# main.net
KiCad netlist of a schematic drawn in Altium Designer
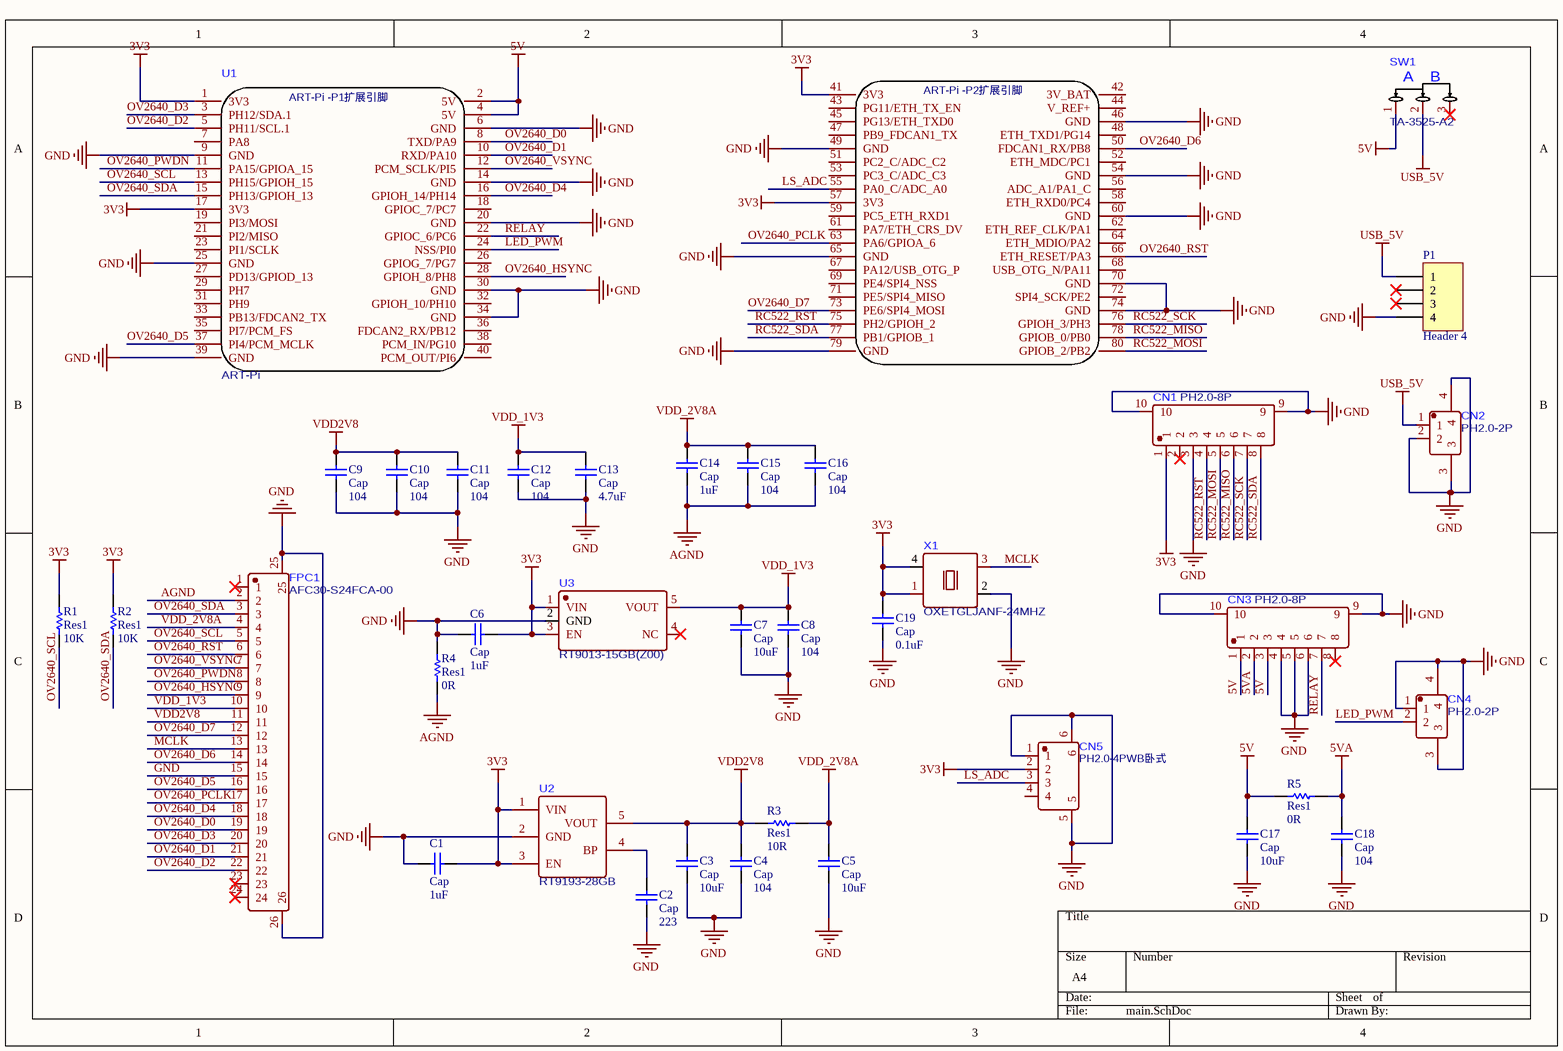
[diagram p0: main.SchDoc]

(export (version "E")
  (design (tool "Eeschema 10.0.6"))
  (components
    (comp (ref "C1")
      (value "Cap")
      (footprint "R0603")
      (description "Capacitor")
      (fields (field (name "ALTIUM_VALUE") "1uF") (field (name "PUBLISHER") "Altium Limited"))
      (libsource (lib "Miscellaneous Devices") (part "Cap"))
    )
    (comp (ref "C2")
      (value "Cap")
      (footprint "R0603")
      (description "Capacitor")
      (fields (field (name "ALTIUM_VALUE") "223") (field (name "PUBLISHER") "Altium Limited"))
      (libsource (lib "Miscellaneous Devices") (part "Cap"))
    )
    (comp (ref "C3")
      (value "Cap")
      (footprint "R0603")
      (description "Capacitor")
      (fields (field (name "ALTIUM_VALUE") "10uF") (field (name "PUBLISHER") "Altium Limited"))
      (libsource (lib "Miscellaneous Devices") (part "Cap"))
    )
    (comp (ref "C4")
      (value "Cap")
      (footprint "R0603")
      (description "Capacitor")
      (fields (field (name "ALTIUM_VALUE") "104") (field (name "PUBLISHER") "Altium Limited"))
      (libsource (lib "Miscellaneous Devices") (part "Cap"))
    )
    (comp (ref "C5")
      (value "Cap")
      (footprint "R0603")
      (description "Capacitor")
      (fields (field (name "ALTIUM_VALUE") "10uF") (field (name "PUBLISHER") "Altium Limited"))
      (libsource (lib "Miscellaneous Devices") (part "Cap"))
    )
    (comp (ref "C6")
      (value "Cap")
      (footprint "R0603")
      (description "Capacitor")
      (fields (field (name "ALTIUM_VALUE") "1uF") (field (name "PUBLISHER") "Altium Limited"))
      (libsource (lib "Miscellaneous Devices") (part "Cap"))
    )
    (comp (ref "C7")
      (value "Cap")
      (footprint "R0603")
      (description "Capacitor")
      (fields (field (name "ALTIUM_VALUE") "10uF") (field (name "PUBLISHER") "Altium Limited"))
      (libsource (lib "Miscellaneous Devices") (part "Cap"))
    )
    (comp (ref "C8")
      (value "Cap")
      (footprint "R0603")
      (description "Capacitor")
      (fields (field (name "ALTIUM_VALUE") "104") (field (name "PUBLISHER") "Altium Limited"))
      (libsource (lib "Miscellaneous Devices") (part "Cap"))
    )
    (comp (ref "C9")
      (value "Cap")
      (footprint "R0603")
      (description "Capacitor")
      (fields (field (name "ALTIUM_VALUE") "104") (field (name "PUBLISHER") "Altium Limited"))
      (libsource (lib "Miscellaneous Devices") (part "Cap"))
    )
    (comp (ref "C10")
      (value "Cap")
      (footprint "R0603")
      (description "Capacitor")
      (fields (field (name "ALTIUM_VALUE") "104") (field (name "PUBLISHER") "Altium Limited"))
      (libsource (lib "Miscellaneous Devices") (part "Cap"))
    )
    (comp (ref "C11")
      (value "Cap")
      (footprint "R0603")
      (description "Capacitor")
      (fields (field (name "ALTIUM_VALUE") "104") (field (name "PUBLISHER") "Altium Limited"))
      (libsource (lib "Miscellaneous Devices") (part "Cap"))
    )
    (comp (ref "C12")
      (value "Cap")
      (footprint "R0603")
      (description "Capacitor")
      (fields (field (name "ALTIUM_VALUE") "104") (field (name "PUBLISHER") "Altium Limited"))
      (libsource (lib "Miscellaneous Devices") (part "Cap"))
    )
    (comp (ref "C13")
      (value "Cap")
      (footprint "R0603")
      (description "Capacitor")
      (fields (field (name "ALTIUM_VALUE") "4.7uF") (field (name "PUBLISHER") "Altium Limited"))
      (libsource (lib "Miscellaneous Devices") (part "Cap"))
    )
    (comp (ref "C14")
      (value "Cap")
      (footprint "R0603")
      (description "Capacitor")
      (fields (field (name "ALTIUM_VALUE") "1uF") (field (name "PUBLISHER") "Altium Limited"))
      (libsource (lib "Miscellaneous Devices") (part "Cap"))
    )
    (comp (ref "C15")
      (value "Cap")
      (footprint "R0603")
      (description "Capacitor")
      (fields (field (name "ALTIUM_VALUE") "104") (field (name "PUBLISHER") "Altium Limited"))
      (libsource (lib "Miscellaneous Devices") (part "Cap"))
    )
    (comp (ref "C16")
      (value "Cap")
      (footprint "R0603")
      (description "Capacitor")
      (fields (field (name "ALTIUM_VALUE") "104") (field (name "PUBLISHER") "Altium Limited"))
      (libsource (lib "Miscellaneous Devices") (part "Cap"))
    )
    (comp (ref "C17")
      (value "Cap")
      (footprint "R0603")
      (description "Capacitor")
      (fields (field (name "ALTIUM_VALUE") "10uF") (field (name "PUBLISHER") "Altium Limited"))
      (libsource (lib "Miscellaneous Devices") (part "Cap"))
    )
    (comp (ref "C18")
      (value "Cap")
      (footprint "R0603")
      (description "Capacitor")
      (fields (field (name "ALTIUM_VALUE") "104") (field (name "PUBLISHER") "Altium Limited"))
      (libsource (lib "Miscellaneous Devices") (part "Cap"))
    )
    (comp (ref "C19")
      (value "Cap")
      (footprint "R0603")
      (description "Capacitor")
      (fields (field (name "ALTIUM_VALUE") "0.1uF") (field (name "PUBLISHER") "Altium Limited"))
      (libsource (lib "Miscellaneous Devices") (part "Cap"))
    )
    (comp (ref "CN1")
      (value "PH2.0-8P")
      (footprint "CONN-SMD_X2016WRS-08-9TSW")
      (libsource (lib "PH2.0-8P_2021-08-20") (part "PH2.0-8P"))
    )
    (comp (ref "CN2")
      (value "PH2.0-2P")
      (footprint "CONN-SMD_PH2.0-1X2PW")
      (libsource (lib "PH2.0-2P_2021-08-20") (part "PH2.0-2P"))
    )
    (comp (ref "CN3")
      (value "PH2.0-8P")
      (footprint "CONN-SMD_X2016WRS-08-9TSW")
      (libsource (lib "PH2.0-8P_2021-08-20") (part "PH2.0-8P"))
    )
    (comp (ref "CN4")
      (value "PH2.0-2P")
      (footprint "CONN-SMD_PH2.0-1X2PW")
      (libsource (lib "PH2.0-2P_2021-08-20") (part "PH2.0-2P"))
    )
    (comp (ref "CN5")
      (value "PH2.0-4PWB卧式")
      (footprint "CONN-SMD_PH2.0-4PWB")
      (libsource (lib "PH2.0-4PWB卧式_2021-08-21") (part "PH2.0-4PWB卧式"))
    )
    (comp (ref "FPC1")
      (value "AFC30-S24FCA-00")
      (footprint "FPC-SMD_AFC30-S24FCA-00")
      (libsource (lib "AFC30-S24FCA-00_2021-08-20") (part "AFC30-S24FCA-00"))
    )
    (comp (ref "P1")
      (value "Header 4")
      (footprint "HDR1X4")
      (description "Header, 4-Pin")
      (fields (field (name "PUBLISHER") "Altium Limited"))
      (libsource (lib "Miscellaneous Connectors") (part "Header 4"))
    )
    (comp (ref "R1")
      (value "Res1")
      (footprint "R0603")
      (description "Resistor")
      (fields (field (name "ALTIUM_VALUE") "10K") (field (name "PUBLISHER") "Altium Limited"))
      (libsource (lib "Miscellaneous Devices") (part "Res1"))
    )
    (comp (ref "R2")
      (value "Res1")
      (footprint "R0603")
      (description "Resistor")
      (fields (field (name "ALTIUM_VALUE") "10K") (field (name "PUBLISHER") "Altium Limited"))
      (libsource (lib "Miscellaneous Devices") (part "Res1"))
    )
    (comp (ref "R3")
      (value "Res1")
      (footprint "R0603")
      (description "Resistor")
      (fields (field (name "ALTIUM_VALUE") "10R") (field (name "PUBLISHER") "Altium Limited"))
      (libsource (lib "Miscellaneous Devices") (part "Res1"))
    )
    (comp (ref "R4")
      (value "Res1")
      (footprint "R0603")
      (description "Resistor")
      (fields (field (name "ALTIUM_VALUE") "0R") (field (name "PUBLISHER") "Altium Limited"))
      (libsource (lib "Miscellaneous Devices") (part "Res1"))
    )
    (comp (ref "R5")
      (value "Res1")
      (footprint "R0603")
      (description "Resistor")
      (fields (field (name "ALTIUM_VALUE") "0R") (field (name "PUBLISHER") "Altium Limited"))
      (libsource (lib "Miscellaneous Devices") (part "Res1"))
    )
    (comp (ref "SW1")
      (value "TA-3525-A2")
      (footprint "SW-SMD_3P-L9.1-W3.5-P2.50-EH6.8")
      (libsource (lib "TA-3525-A2_2021-08-20") (part "TA-3525-A2"))
    )
    (comp (ref "U1")
      (value "ART-Pi")
      (footprint "PCBComponent_1 - duplicate")
      (libsource (lib "ART-Pi") (part "ART-Pi"))
    )
    (comp (ref "U2")
      (value "RT9193-28GB")
      (footprint "SOT-23-5_L3.0-W1.7-P0.95-LS2.8-BR")
      (libsource (lib "RT9193-28GB_2021-08-20") (part "RT9193-28GB"))
    )
    (comp (ref "U3")
      (value "RT9013-15GB(Z00)")
      (footprint "SOT-23-5_L3.0-W1.7-P0.95-LS2.8-BR")
      (libsource (lib "RT9013-15GB(Z00)_2021-08-20") (part "RT9013-15GB(Z00)"))
    )
    (comp (ref "X1")
      (value "OXETGLJANF-24MHZ")
      (footprint "OSC-SMD_4P-L3.2-W2.5-BL")
      (libsource (lib "OXETGLJANF-24MHZ_2021-08-21") (part "OXETGLJANF-24MHZ"))
    )
  )
  (nets
    (net (code "1") (name "/LED_PWM") (class "Default")
      (node (ref "CN4") (pin "2") (pinfunction "2_2") (pintype "passive"))
      (node (ref "U1") (pin "24") (pinfunction "NSS/PI0_24") (pintype "passive"))
    )
    (net (code "2") (name "/LS_ADC") (class "Default")
      (node (ref "CN5") (pin "3") (pinfunction "3_3") (pintype "passive"))
      (node (ref "U1") (pin "55") (pinfunction "PA0_C/ADC_A0_55") (pintype "passive"))
    )
    (net (code "3") (name "/MCLK") (class "Default")
      (node (ref "FPC1") (pin "13") (pinfunction "13_13") (pintype "passive"))
      (node (ref "X1") (pin "3") (pinfunction "OUT_3") (pintype "passive"))
    )
    (net (code "4") (name "/OV2640_D0") (class "Default")
      (node (ref "FPC1") (pin "19") (pinfunction "19_19") (pintype "passive"))
      (node (ref "U1") (pin "8") (pinfunction "TXD/PA9_8") (pintype "passive"))
    )
    (net (code "5") (name "/OV2640_D1") (class "Default")
      (node (ref "FPC1") (pin "21") (pinfunction "21_21") (pintype "passive"))
      (node (ref "U1") (pin "10") (pinfunction "RXD/PA10_10") (pintype "passive"))
    )
    (net (code "6") (name "/OV2640_D2") (class "Default")
      (node (ref "FPC1") (pin "22") (pinfunction "22_22") (pintype "passive"))
      (node (ref "U1") (pin "5") (pinfunction "PH11/SCL.1_5") (pintype "passive"))
    )
    (net (code "7") (name "/OV2640_D3") (class "Default")
      (node (ref "FPC1") (pin "20") (pinfunction "20_20") (pintype "passive"))
      (node (ref "U1") (pin "3") (pinfunction "PH12/SDA.1_3") (pintype "passive"))
    )
    (net (code "8") (name "/OV2640_D4") (class "Default")
      (node (ref "FPC1") (pin "18") (pinfunction "18_18") (pintype "passive"))
      (node (ref "U1") (pin "16") (pinfunction "GPIOH_14/PH14_16") (pintype "passive"))
    )
    (net (code "9") (name "/OV2640_D5") (class "Default")
      (node (ref "FPC1") (pin "16") (pinfunction "16_16") (pintype "passive"))
      (node (ref "U1") (pin "37") (pinfunction "PI4/PCM_MCLK_37") (pintype "passive"))
    )
    (net (code "10") (name "/OV2640_D6") (class "Default")
      (node (ref "FPC1") (pin "14") (pinfunction "14_14") (pintype "passive"))
      (node (ref "U1") (pin "50") (pinfunction "FDCAN1_RX/PB8_50") (pintype "passive"))
    )
    (net (code "11") (name "/OV2640_D7") (class "Default")
      (node (ref "FPC1") (pin "12") (pinfunction "12_12") (pintype "passive"))
      (node (ref "U1") (pin "73") (pinfunction "PE6/SPI4_MOSI_73") (pintype "passive"))
    )
    (net (code "12") (name "/OV2640_HSYNC") (class "Default")
      (node (ref "FPC1") (pin "9") (pinfunction "9_9") (pintype "passive"))
      (node (ref "U1") (pin "28") (pinfunction "GPIOH_8/PH8_28") (pintype "passive"))
    )
    (net (code "13") (name "/OV2640_PCLK") (class "Default")
      (node (ref "FPC1") (pin "17") (pinfunction "17_17") (pintype "passive"))
      (node (ref "U1") (pin "63") (pinfunction "PA6/GPIOA_6_63") (pintype "passive"))
    )
    (net (code "14") (name "/OV2640_PWDN") (class "Default")
      (node (ref "FPC1") (pin "8") (pinfunction "8_8") (pintype "passive"))
      (node (ref "U1") (pin "11") (pinfunction "PA15/GPIOA_15_11") (pintype "passive"))
    )
    (net (code "15") (name "/OV2640_RST") (class "Default")
      (node (ref "FPC1") (pin "6") (pinfunction "6_6") (pintype "passive"))
      (node (ref "U1") (pin "66") (pinfunction "ETH_RESET/PA3_66") (pintype "passive"))
    )
    (net (code "16") (name "/OV2640_SCL") (class "Default")
      (node (ref "FPC1") (pin "5") (pinfunction "5_5") (pintype "passive"))
      (node (ref "R1") (pin "1") (pinfunction "1_1") (pintype "passive"))
      (node (ref "U1") (pin "13") (pinfunction "PH15/GPIOH_15_13") (pintype "passive"))
    )
    (net (code "17") (name "/OV2640_SDA") (class "Default")
      (node (ref "FPC1") (pin "3") (pinfunction "3_3") (pintype "passive"))
      (node (ref "R2") (pin "1") (pinfunction "1_1") (pintype "passive"))
      (node (ref "U1") (pin "15") (pinfunction "PH13/GPIOH_13_15") (pintype "passive"))
    )
    (net (code "18") (name "/OV2640_VSYNC") (class "Default")
      (node (ref "FPC1") (pin "7") (pinfunction "7_7") (pintype "passive"))
      (node (ref "U1") (pin "12") (pinfunction "PCM_SCLK/PI5_12") (pintype "passive"))
    )
    (net (code "19") (name "/RC522_MISO") (class "Default")
      (node (ref "CN1") (pin "6") (pinfunction "6_6") (pintype "passive"))
      (node (ref "U1") (pin "78") (pinfunction "GPIOB_0/PB0_78") (pintype "passive"))
    )
    (net (code "20") (name "/RC522_MOSI") (class "Default")
      (node (ref "CN1") (pin "5") (pinfunction "5_5") (pintype "passive"))
      (node (ref "U1") (pin "80") (pinfunction "GPIOB_2/PB2_80") (pintype "passive"))
    )
    (net (code "21") (name "/RC522_RST") (class "Default")
      (node (ref "CN1") (pin "4") (pinfunction "4_4") (pintype "passive"))
      (node (ref "U1") (pin "75") (pinfunction "PH2/GPIOH_2_75") (pintype "passive"))
    )
    (net (code "22") (name "/RC522_SCK") (class "Default")
      (node (ref "CN1") (pin "7") (pinfunction "7_7") (pintype "passive"))
      (node (ref "U1") (pin "76") (pinfunction "GPIOH_3/PH3_76") (pintype "passive"))
    )
    (net (code "23") (name "/RC522_SDA") (class "Default")
      (node (ref "CN1") (pin "8") (pinfunction "8_8") (pintype "passive"))
      (node (ref "U1") (pin "77") (pinfunction "PB1/GPIOB_1_77") (pintype "passive"))
    )
    (net (code "24") (name "/RELAY") (class "Default")
      (node (ref "CN3") (pin "7") (pinfunction "7_7") (pintype "passive"))
      (node (ref "U1") (pin "22") (pinfunction "GPIOC_6/PC6_22") (pintype "passive"))
    )
    (net (code "25") (name "3V3") (class "Default")
      (node (ref "C1") (pin "1") (pinfunction "1_1") (pintype "passive"))
      (node (ref "C19") (pin "2") (pinfunction "2_2") (pintype "passive"))
      (node (ref "C6") (pin "1") (pinfunction "1_1") (pintype "passive"))
      (node (ref "CN1") (pin "1") (pinfunction "1_1") (pintype "passive"))
      (node (ref "CN5") (pin "2") (pinfunction "2_2") (pintype "passive"))
      (node (ref "R1") (pin "2") (pinfunction "2_2") (pintype "passive"))
      (node (ref "R2") (pin "2") (pinfunction "2_2") (pintype "passive"))
      (node (ref "U1") (pin "1") (pinfunction "3V3_1") (pintype "passive"))
      (node (ref "U1") (pin "17") (pinfunction "3V3_17") (pintype "passive"))
      (node (ref "U1") (pin "41") (pinfunction "3V3_41") (pintype "passive"))
      (node (ref "U1") (pin "57") (pinfunction "3V3_57") (pintype "passive"))
      (node (ref "U2") (pin "1") (pinfunction "VIN_1") (pintype "passive"))
      (node (ref "U2") (pin "3") (pinfunction "EN_3") (pintype "passive"))
      (node (ref "U3") (pin "1") (pinfunction "VIN_1") (pintype "passive"))
      (node (ref "U3") (pin "3") (pinfunction "EN_3") (pintype "passive"))
      (node (ref "X1") (pin "1") (pinfunction "tri_1") (pintype "passive"))
      (node (ref "X1") (pin "4") (pinfunction "VCC_4") (pintype "passive"))
    )
    (net (code "26") (name "5V") (class "Default")
      (node (ref "C17") (pin "2") (pinfunction "2_2") (pintype "passive"))
      (node (ref "CN3") (pin "1") (pinfunction "1_1") (pintype "passive"))
      (node (ref "CN3") (pin "3") (pinfunction "3_3") (pintype "passive"))
      (node (ref "R5") (pin "1") (pinfunction "1_1") (pintype "passive"))
      (node (ref "SW1") (pin "1") (pinfunction "1_1") (pintype "passive"))
      (node (ref "U1") (pin "2") (pinfunction "5V_2") (pintype "passive"))
      (node (ref "U1") (pin "4") (pinfunction "5V_4") (pintype "passive"))
    )
    (net (code "27") (name "5VA") (class "Default")
      (node (ref "C18") (pin "2") (pinfunction "2_2") (pintype "passive"))
      (node (ref "CN3") (pin "2") (pinfunction "2_2") (pintype "passive"))
      (node (ref "R5") (pin "2") (pinfunction "2_2") (pintype "passive"))
    )
    (net (code "28") (name "AGND") (class "Default")
      (node (ref "C14") (pin "1") (pinfunction "1_1") (pintype "passive"))
      (node (ref "C15") (pin "1") (pinfunction "1_1") (pintype "passive"))
      (node (ref "C16") (pin "1") (pinfunction "1_1") (pintype "passive"))
      (node (ref "FPC1") (pin "2") (pinfunction "2_2") (pintype "passive"))
      (node (ref "R4") (pin "1") (pinfunction "1_1") (pintype "passive"))
    )
    (net (code "29") (name "GND") (class "Default")
      (node (ref "C1") (pin "2") (pinfunction "2_2") (pintype "passive"))
      (node (ref "C10") (pin "1") (pinfunction "1_1") (pintype "passive"))
      (node (ref "C11") (pin "1") (pinfunction "1_1") (pintype "passive"))
      (node (ref "C12") (pin "1") (pinfunction "1_1") (pintype "passive"))
      (node (ref "C13") (pin "1") (pinfunction "1_1") (pintype "passive"))
      (node (ref "C17") (pin "1") (pinfunction "1_1") (pintype "passive"))
      (node (ref "C18") (pin "1") (pinfunction "1_1") (pintype "passive"))
      (node (ref "C19") (pin "1") (pinfunction "1_1") (pintype "passive"))
      (node (ref "C2") (pin "1") (pinfunction "1_1") (pintype "passive"))
      (node (ref "C3") (pin "1") (pinfunction "1_1") (pintype "passive"))
      (node (ref "C4") (pin "1") (pinfunction "1_1") (pintype "passive"))
      (node (ref "C5") (pin "1") (pinfunction "1_1") (pintype "passive"))
      (node (ref "C6") (pin "2") (pinfunction "2_2") (pintype "passive"))
      (node (ref "C7") (pin "1") (pinfunction "1_1") (pintype "passive"))
      (node (ref "C8") (pin "1") (pinfunction "1_1") (pintype "passive"))
      (node (ref "C9") (pin "1") (pinfunction "1_1") (pintype "passive"))
      (node (ref "CN1") (pin "10") (pinfunction "10_10") (pintype "passive"))
      (node (ref "CN1") (pin "3") (pinfunction "3_3") (pintype "passive"))
      (node (ref "CN1") (pin "9") (pinfunction "9_9") (pintype "passive"))
      (node (ref "CN2") (pin "2") (pinfunction "2_2") (pintype "passive"))
      (node (ref "CN2") (pin "3") (pinfunction "3_3") (pintype "passive"))
      (node (ref "CN2") (pin "4") (pinfunction "4_4") (pintype "passive"))
      (node (ref "CN3") (pin "10") (pinfunction "10_10") (pintype "passive"))
      (node (ref "CN3") (pin "4") (pinfunction "4_4") (pintype "passive"))
      (node (ref "CN3") (pin "5") (pinfunction "5_5") (pintype "passive"))
      (node (ref "CN3") (pin "6") (pinfunction "6_6") (pintype "passive"))
      (node (ref "CN3") (pin "9") (pinfunction "9_9") (pintype "passive"))
      (node (ref "CN4") (pin "1") (pinfunction "1_1") (pintype "passive"))
      (node (ref "CN4") (pin "3") (pinfunction "3_3") (pintype "passive"))
      (node (ref "CN4") (pin "4") (pinfunction "4_4") (pintype "passive"))
      (node (ref "CN5") (pin "1") (pinfunction "1_1") (pintype "passive"))
      (node (ref "CN5") (pin "5") (pinfunction "5_5") (pintype "passive"))
      (node (ref "CN5") (pin "6") (pinfunction "6_6") (pintype "passive"))
      (node (ref "FPC1") (pin "15") (pinfunction "15_15") (pintype "passive"))
      (node (ref "FPC1") (pin "25") (pinfunction "25_25") (pintype "passive"))
      (node (ref "FPC1") (pin "26") (pinfunction "26_26") (pintype "passive"))
      (node (ref "P1") (pin "4") (pinfunction "4_4") (pintype "passive"))
      (node (ref "R4") (pin "2") (pinfunction "2_2") (pintype "passive"))
      (node (ref "U1") (pin "14") (pinfunction "GND_14") (pintype "passive"))
      (node (ref "U1") (pin "20") (pinfunction "GND_20") (pintype "passive"))
      (node (ref "U1") (pin "25") (pinfunction "GND_25") (pintype "passive"))
      (node (ref "U1") (pin "30") (pinfunction "GND_30") (pintype "passive"))
      (node (ref "U1") (pin "34") (pinfunction "GND_34") (pintype "passive"))
      (node (ref "U1") (pin "39") (pinfunction "GND_39") (pintype "passive"))
      (node (ref "U1") (pin "46") (pinfunction "GND_46") (pintype "passive"))
      (node (ref "U1") (pin "49") (pinfunction "GND_49") (pintype "passive"))
      (node (ref "U1") (pin "54") (pinfunction "GND_54") (pintype "passive"))
      (node (ref "U1") (pin "6") (pinfunction "GND_6") (pintype "passive"))
      (node (ref "U1") (pin "60") (pinfunction "GND_60") (pintype "passive"))
      (node (ref "U1") (pin "65") (pinfunction "GND_65") (pintype "passive"))
      (node (ref "U1") (pin "70") (pinfunction "GND_70") (pintype "passive"))
      (node (ref "U1") (pin "74") (pinfunction "GND_74") (pintype "passive"))
      (node (ref "U1") (pin "79") (pinfunction "GND_79") (pintype "passive"))
      (node (ref "U1") (pin "9") (pinfunction "GND_9") (pintype "passive"))
      (node (ref "U2") (pin "2") (pinfunction "GND_2") (pintype "passive"))
      (node (ref "U3") (pin "2") (pinfunction "GND_2") (pintype "passive"))
      (node (ref "X1") (pin "2") (pinfunction "GND_2") (pintype "passive"))
    )
    (net (code "30") (name "Net-(U2-BP)") (class "Default")
      (node (ref "C2") (pin "2") (pinfunction "2_2") (pintype "passive"))
      (node (ref "U2") (pin "4") (pinfunction "BP_4") (pintype "passive"))
    )
    (net (code "31") (name "USB_5V") (class "Default")
      (node (ref "CN2") (pin "1") (pinfunction "1_1") (pintype "passive"))
      (node (ref "P1") (pin "1") (pinfunction "1_1") (pintype "passive"))
      (node (ref "SW1") (pin "2") (pinfunction "2_2") (pintype "passive"))
    )
    (net (code "32") (name "VDD2V8") (class "Default")
      (node (ref "C10") (pin "2") (pinfunction "2_2") (pintype "passive"))
      (node (ref "C11") (pin "2") (pinfunction "2_2") (pintype "passive"))
      (node (ref "C3") (pin "2") (pinfunction "2_2") (pintype "passive"))
      (node (ref "C4") (pin "2") (pinfunction "2_2") (pintype "passive"))
      (node (ref "C9") (pin "2") (pinfunction "2_2") (pintype "passive"))
      (node (ref "FPC1") (pin "11") (pinfunction "11_11") (pintype "passive"))
      (node (ref "R3") (pin "1") (pinfunction "1_1") (pintype "passive"))
      (node (ref "U2") (pin "5") (pinfunction "VOUT_5") (pintype "passive"))
    )
    (net (code "33") (name "VDD_1V3") (class "Default")
      (node (ref "C12") (pin "2") (pinfunction "2_2") (pintype "passive"))
      (node (ref "C13") (pin "2") (pinfunction "2_2") (pintype "passive"))
      (node (ref "C7") (pin "2") (pinfunction "2_2") (pintype "passive"))
      (node (ref "C8") (pin "2") (pinfunction "2_2") (pintype "passive"))
      (node (ref "FPC1") (pin "10") (pinfunction "10_10") (pintype "passive"))
      (node (ref "U3") (pin "5") (pinfunction "VOUT_5") (pintype "passive"))
    )
    (net (code "34") (name "VDD_2V8A") (class "Default")
      (node (ref "C14") (pin "2") (pinfunction "2_2") (pintype "passive"))
      (node (ref "C15") (pin "2") (pinfunction "2_2") (pintype "passive"))
      (node (ref "C16") (pin "2") (pinfunction "2_2") (pintype "passive"))
      (node (ref "C5") (pin "2") (pinfunction "2_2") (pintype "passive"))
      (node (ref "FPC1") (pin "4") (pinfunction "4_4") (pintype "passive"))
      (node (ref "R3") (pin "2") (pinfunction "2_2") (pintype "passive"))
    )
    (net (code "35") (name "unconnected-(CN1-Pad2)") (class "Default")
      (node (ref "CN1") (pin "2") (pinfunction "2_2") (pintype "passive+no_connect"))
    )
    (net (code "36") (name "unconnected-(CN3-Pad8)") (class "Default")
      (node (ref "CN3") (pin "8") (pinfunction "8_8") (pintype "passive+no_connect"))
    )
    (net (code "37") (name "unconnected-(CN5-Pad4)") (class "Default")
      (node (ref "CN5") (pin "4") (pinfunction "4_4") (pintype "passive"))
    )
    (net (code "38") (name "unconnected-(FPC1-Pad1)") (class "Default")
      (node (ref "FPC1") (pin "1") (pinfunction "1_1") (pintype "passive+no_connect"))
    )
    (net (code "39") (name "unconnected-(FPC1-Pad23)") (class "Default")
      (node (ref "FPC1") (pin "23") (pinfunction "23_23") (pintype "passive+no_connect"))
    )
    (net (code "40") (name "unconnected-(FPC1-Pad24)") (class "Default")
      (node (ref "FPC1") (pin "24") (pinfunction "24_24") (pintype "passive+no_connect"))
    )
    (net (code "41") (name "unconnected-(P1-Pad2)") (class "Default")
      (node (ref "P1") (pin "2") (pinfunction "2_2") (pintype "passive+no_connect"))
    )
    (net (code "42") (name "unconnected-(P1-Pad3)") (class "Default")
      (node (ref "P1") (pin "3") (pinfunction "3_3") (pintype "passive+no_connect"))
    )
    (net (code "43") (name "unconnected-(SW1-Pad3)") (class "Default")
      (node (ref "SW1") (pin "3") (pinfunction "3_3") (pintype "passive+no_connect"))
    )
    (net (code "44") (name "unconnected-(U1-3V_BAT-Pad42)") (class "Default")
      (node (ref "U1") (pin "42") (pinfunction "3V_BAT_42") (pintype "passive"))
    )
    (net (code "45") (name "unconnected-(U1-ADC_A1{slash}PA1_C-Pad56)") (class "Default")
      (node (ref "U1") (pin "56") (pinfunction "ADC_A1/PA1_C_56") (pintype "passive"))
    )
    (net (code "46") (name "unconnected-(U1-ETH_MDC{slash}PC1-Pad52)") (class "Default")
      (node (ref "U1") (pin "52") (pinfunction "ETH_MDC/PC1_52") (pintype "passive"))
    )
    (net (code "47") (name "unconnected-(U1-ETH_MDIO{slash}PA2-Pad64)") (class "Default")
      (node (ref "U1") (pin "64") (pinfunction "ETH_MDIO/PA2_64") (pintype "passive"))
    )
    (net (code "48") (name "unconnected-(U1-ETH_REF_CLK{slash}PA1-Pad62)") (class "Default")
      (node (ref "U1") (pin "62") (pinfunction "ETH_REF_CLK/PA1_62") (pintype "passive"))
    )
    (net (code "49") (name "unconnected-(U1-ETH_RXD0{slash}PC4-Pad58)") (class "Default")
      (node (ref "U1") (pin "58") (pinfunction "ETH_RXD0/PC4_58") (pintype "passive"))
    )
    (net (code "50") (name "unconnected-(U1-ETH_TXD1{slash}PG14-Pad48)") (class "Default")
      (node (ref "U1") (pin "48") (pinfunction "ETH_TXD1/PG14_48") (pintype "passive"))
    )
    (net (code "51") (name "unconnected-(U1-FDCAN2_RX{slash}PB12-Pad36)") (class "Default")
      (node (ref "U1") (pin "36") (pinfunction "FDCAN2_RX/PB12_36") (pintype "passive"))
    )
    (net (code "52") (name "unconnected-(U1-GPIOC_7{slash}PC7-Pad18)") (class "Default")
      (node (ref "U1") (pin "18") (pinfunction "GPIOC_7/PC7_18") (pintype "passive"))
    )
    (net (code "53") (name "unconnected-(U1-GPIOG_7{slash}PG7-Pad26)") (class "Default")
      (node (ref "U1") (pin "26") (pinfunction "GPIOG_7/PG7_26") (pintype "passive"))
    )
    (net (code "54") (name "unconnected-(U1-GPIOH_10{slash}PH10-Pad32)") (class "Default")
      (node (ref "U1") (pin "32") (pinfunction "GPIOH_10/PH10_32") (pintype "passive"))
    )
    (net (code "55") (name "unconnected-(U1-PA7{slash}ETH_CRS_DV-Pad61)") (class "Default")
      (node (ref "U1") (pin "61") (pinfunction "PA7/ETH_CRS_DV_61") (pintype "passive"))
    )
    (net (code "56") (name "unconnected-(U1-PA8-Pad7)") (class "Default")
      (node (ref "U1") (pin "7") (pinfunction "PA8_7") (pintype "passive"))
    )
    (net (code "57") (name "unconnected-(U1-PA12{slash}USB_OTG_P-Pad67)") (class "Default")
      (node (ref "U1") (pin "67") (pinfunction "PA12/USB_OTG_P_67") (pintype "passive"))
    )
    (net (code "58") (name "unconnected-(U1-PB9_FDCAN1_TX-Pad47)") (class "Default")
      (node (ref "U1") (pin "47") (pinfunction "PB9_FDCAN1_TX_47") (pintype "passive"))
    )
    (net (code "59") (name "unconnected-(U1-PB13{slash}FDCAN2_TX-Pad33)") (class "Default")
      (node (ref "U1") (pin "33") (pinfunction "PB13/FDCAN2_TX_33") (pintype "passive"))
    )
    (net (code "60") (name "unconnected-(U1-PC2_C{slash}ADC_C2-Pad51)") (class "Default")
      (node (ref "U1") (pin "51") (pinfunction "PC2_C/ADC_C2_51") (pintype "passive"))
    )
    (net (code "61") (name "unconnected-(U1-PC3_C{slash}ADC_C3-Pad53)") (class "Default")
      (node (ref "U1") (pin "53") (pinfunction "PC3_C/ADC_C3_53") (pintype "passive"))
    )
    (net (code "62") (name "unconnected-(U1-PC5_ETH_RXD1-Pad59)") (class "Default")
      (node (ref "U1") (pin "59") (pinfunction "PC5_ETH_RXD1_59") (pintype "passive"))
    )
    (net (code "63") (name "unconnected-(U1-PCM_IN{slash}PG10-Pad38)") (class "Default")
      (node (ref "U1") (pin "38") (pinfunction "PCM_IN/PG10_38") (pintype "passive"))
    )
    (net (code "64") (name "unconnected-(U1-PCM_OUT{slash}PI6-Pad40)") (class "Default")
      (node (ref "U1") (pin "40") (pinfunction "PCM_OUT/PI6_40") (pintype "passive"))
    )
    (net (code "65") (name "unconnected-(U1-PD13{slash}GPIOD_13-Pad27)") (class "Default")
      (node (ref "U1") (pin "27") (pinfunction "PD13/GPIOD_13_27") (pintype "passive"))
    )
    (net (code "66") (name "unconnected-(U1-PE4{slash}SPI4_NSS-Pad69)") (class "Default")
      (node (ref "U1") (pin "69") (pinfunction "PE4/SPI4_NSS_69") (pintype "passive"))
    )
    (net (code "67") (name "unconnected-(U1-PE5{slash}SPI4_MISO-Pad71)") (class "Default")
      (node (ref "U1") (pin "71") (pinfunction "PE5/SPI4_MISO_71") (pintype "passive"))
    )
    (net (code "68") (name "unconnected-(U1-PG11{slash}ETH_TX_EN-Pad43)") (class "Default")
      (node (ref "U1") (pin "43") (pinfunction "PG11/ETH_TX_EN_43") (pintype "passive"))
    )
    (net (code "69") (name "unconnected-(U1-PG13{slash}ETH_TXD0-Pad45)") (class "Default")
      (node (ref "U1") (pin "45") (pinfunction "PG13/ETH_TXD0_45") (pintype "passive"))
    )
    (net (code "70") (name "unconnected-(U1-PH7-Pad29)") (class "Default")
      (node (ref "U1") (pin "29") (pinfunction "PH7_29") (pintype "passive"))
    )
    (net (code "71") (name "unconnected-(U1-PH9-Pad31)") (class "Default")
      (node (ref "U1") (pin "31") (pinfunction "PH9_31") (pintype "passive"))
    )
    (net (code "72") (name "unconnected-(U1-PI1{slash}SCLK-Pad23)") (class "Default")
      (node (ref "U1") (pin "23") (pinfunction "PI1/SCLK_23") (pintype "passive"))
    )
    (net (code "73") (name "unconnected-(U1-PI2{slash}MISO-Pad21)") (class "Default")
      (node (ref "U1") (pin "21") (pinfunction "PI2/MISO_21") (pintype "passive"))
    )
    (net (code "74") (name "unconnected-(U1-PI3{slash}MOSI-Pad19)") (class "Default")
      (node (ref "U1") (pin "19") (pinfunction "PI3/MOSI_19") (pintype "passive"))
    )
    (net (code "75") (name "unconnected-(U1-PI7{slash}PCM_FS-Pad35)") (class "Default")
      (node (ref "U1") (pin "35") (pinfunction "PI7/PCM_FS_35") (pintype "passive"))
    )
    (net (code "76") (name "unconnected-(U1-SPI4_SCK{slash}PE2-Pad72)") (class "Default")
      (node (ref "U1") (pin "72") (pinfunction "SPI4_SCK/PE2_72") (pintype "passive"))
    )
    (net (code "77") (name "unconnected-(U1-USB_OTG_N{slash}PA11-Pad68)") (class "Default")
      (node (ref "U1") (pin "68") (pinfunction "USB_OTG_N/PA11_68") (pintype "passive"))
    )
    (net (code "78") (name "unconnected-(U1-V_REF+-Pad44)") (class "Default")
      (node (ref "U1") (pin "44") (pinfunction "V_REF+_44") (pintype "passive"))
    )
    (net (code "79") (name "unconnected-(U3-NC-Pad4)") (class "Default")
      (node (ref "U3") (pin "4") (pinfunction "NC_4") (pintype "passive+no_connect"))
    )
  )
)
